# 03-_Power_Supply.net
KiCad netlist of a schematic drawn in Altium Designer
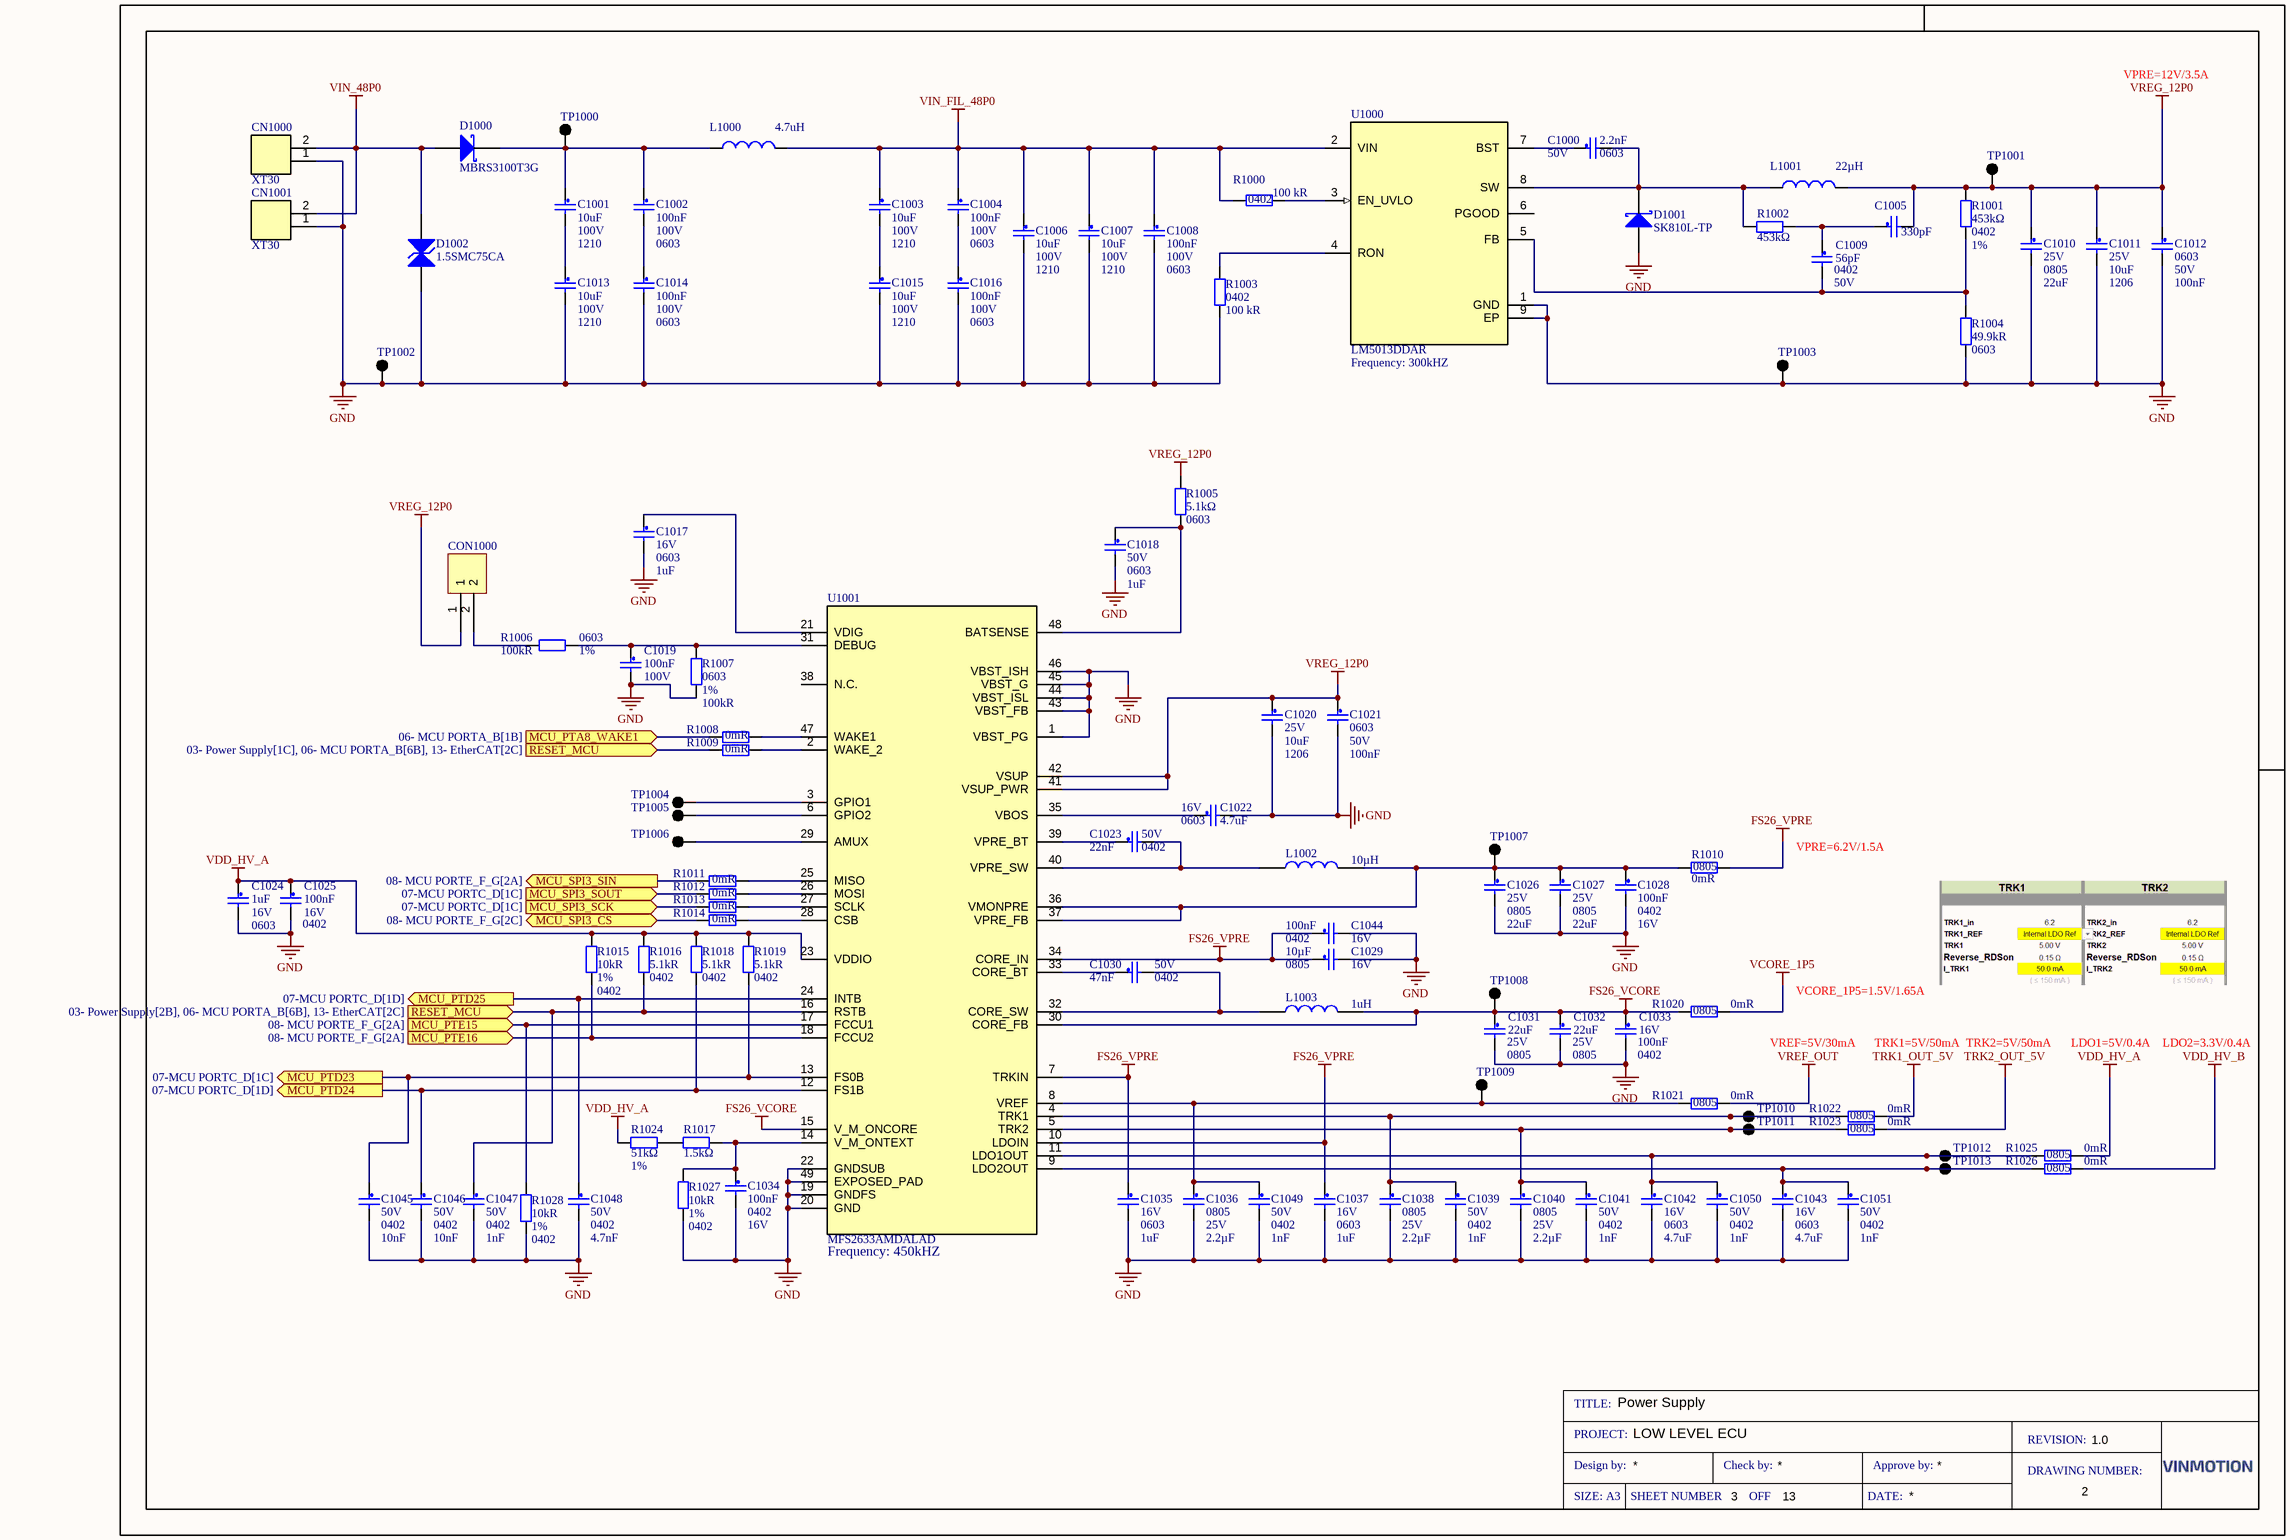
[diagram p0: 03- Power Supply.SchDoc]

(export (version "E")
  (design (tool "Eeschema 10.0.6"))
  (components
    (comp (ref "C1000")
      (value "CL10B222KB8WPNC")
      (footprint "CAP0603")
      (description "CAP CER 2200PF 50V X7R 0603")
      (fields
        (field (name "TOLERANCE") "10%")
        (field (name "VOLTAGE RATING") "50V")
        (field (name "CASE/PACKAGE") "0603")
        (field (name "CAPACITANCE") "2.2nF")
      )
      (libsource (lib "VMO_Lib") (part "CMP-00248-3"))
    )
    (comp (ref "C1001")
      (value "10uF")
      (footprint "CAP1210")
      (description "CAP CER 10UF 100V X7R 1210")
      (fields
        (field (name "MANUFACTURER") "TDK")
        (field (name "MANUFACTURER PART NUMBER") "C3225X7R2A106K250AC")
        (field (name "DC VOLTAGE RATED") "100V")
        (field (name "PACKAGE") "1210")
      )
      (libsource (lib "VMO_Lib") (part "CMP-01079-1"))
    )
    (comp (ref "C1002")
      (value "100nF")
      (footprint "CAP0603")
      (description "CAP CER 0.1UF 100V X7R 0603")
      (fields
        (field (name "MANUFACTURER") "Yageo")
        (field (name "MANUFACTURER PART NUMBER") "CC0603KRX7R0BB104")
        (field (name "RATED DC VOLTAGE (URDC)") "100V")
        (field (name "CASE/PACKAGE") "0603")
      )
      (libsource (lib "VMO_Lib") (part "CMP-01080-1"))
    )
    (comp (ref "C1003")
      (value "10uF")
      (footprint "CAP1210")
      (description "CAP CER 10UF 100V X7R 1210")
      (fields
        (field (name "MANUFACTURER") "TDK")
        (field (name "MANUFACTURER PART NUMBER") "C3225X7R2A106K250AC")
        (field (name "DC VOLTAGE RATED") "100V")
        (field (name "PACKAGE") "1210")
      )
      (libsource (lib "VMO_Lib") (part "CMP-01079-1"))
    )
    (comp (ref "C1004")
      (value "100nF")
      (footprint "CAP0603")
      (description "CAP CER 0.1UF 100V X7R 0603")
      (fields
        (field (name "MANUFACTURER") "Yageo")
        (field (name "MANUFACTURER PART NUMBER") "CC0603KRX7R0BB104")
        (field (name "RATED DC VOLTAGE (URDC)") "100V")
        (field (name "CASE/PACKAGE") "0603")
      )
      (libsource (lib "VMO_Lib") (part "CMP-01080-1"))
    )
    (comp (ref "C1005")
      (value "GCM1885C2A331JA16D")
      (footprint "CAP0603")
      (description "CAP CER 330pF 100V 5% C0G 0603 SMD")
      (fields (field (name "TOLERANCE") "5%") (field (name "CAPACITANCE") "330pF"))
      (libsource (lib "VMO_Lib") (part "CMP-00223-4"))
    )
    (comp (ref "C1006")
      (value "10uF")
      (footprint "CAP1210")
      (description "CAP CER 10UF 100V X7R 1210")
      (fields
        (field (name "MANUFACTURER") "TDK")
        (field (name "MANUFACTURER PART NUMBER") "C3225X7R2A106K250AC")
        (field (name "DC VOLTAGE RATED") "100V")
        (field (name "PACKAGE") "1210")
      )
      (libsource (lib "VMO_Lib") (part "CMP-01079-1"))
    )
    (comp (ref "C1007")
      (value "10uF")
      (footprint "CAP1210")
      (description "CAP CER 10UF 100V X7R 1210")
      (fields
        (field (name "MANUFACTURER") "TDK")
        (field (name "MANUFACTURER PART NUMBER") "C3225X7R2A106K250AC")
        (field (name "DC VOLTAGE RATED") "100V")
        (field (name "PACKAGE") "1210")
      )
      (libsource (lib "VMO_Lib") (part "CMP-01079-1"))
    )
    (comp (ref "C1008")
      (value "100nF")
      (footprint "CAP0603")
      (description "CAP CER 0.1UF 100V X7R 0603")
      (fields
        (field (name "MANUFACTURER") "Yageo")
        (field (name "MANUFACTURER PART NUMBER") "CC0603KRX7R0BB104")
        (field (name "RATED DC VOLTAGE (URDC)") "100V")
        (field (name "CASE/PACKAGE") "0603")
      )
      (libsource (lib "VMO_Lib") (part "CMP-01080-1"))
    )
    (comp (ref "C1009")
      (value "GCM1555C1H560JA16D")
      (footprint "CAP0402")
      (description "CAP CER 56PF 50V C0G/NP0 0402")
      (fields
        (field (name "TOLERANCE") "5%")
        (field (name "CASE/PACKAGE") "0402")
        (field (name "VOLTAGE RATING") "50V")
        (field (name "CAPACITANCE") "56pF")
      )
      (libsource (lib "VMO_Lib") (part "CMP-00911-1"))
    )
    (comp (ref "C1010")
      (value "GRM21BR61E226ME44K")
      (footprint "CAP0805")
      (description "CAP CER 22uF 25V 20% X5R 0805 SMD")
      (fields
        (field (name "TOLERANCE") "20%")
        (field (name "VOLTAGE RATING") "25V")
        (field (name "CASE/PACKAGE") "0805")
        (field (name "CAPACITANCE") "22uF")
      )
      (libsource (lib "VMO_Lib") (part "CMP-ROOT-0068-6"))
    )
    (comp (ref "C1011")
      (value "GCM31CC71E106KA03L")
      (footprint "CAP1206")
      (description "CAP CER 10UF 25V X7S 1206")
      (fields
        (field (name "VOLTAGE RATING (DC)") "25V")
        (field (name "CAPACITANCE") "10uF")
        (field (name "TOLERANCE") "10%")
        (field (name "CASE CODE (IMPERIAL)") "1206")
      )
      (libsource (lib "VMO_Lib") (part "CMP-00214-1"))
    )
    (comp (ref "C1012")
      (value "CL10B104KB8WPNC")
      (footprint "CAP0603")
      (description "CAP CER 0.1UF 50V X7R 0603")
      (fields
        (field (name "TOLERANCE") "10%")
        (field (name "CASE/PACKAGE") "0603")
        (field (name "VOLTAGE RATING") "50V")
        (field (name "CAPACITANCE") "100nF")
      )
      (libsource (lib "VMO_Lib") (part "CMP-00005-5"))
    )
    (comp (ref "C1013")
      (value "10uF")
      (footprint "CAP1210")
      (description "CAP CER 10UF 100V X7R 1210")
      (fields
        (field (name "MANUFACTURER") "TDK")
        (field (name "MANUFACTURER PART NUMBER") "C3225X7R2A106K250AC")
        (field (name "DC VOLTAGE RATED") "100V")
        (field (name "PACKAGE") "1210")
      )
      (libsource (lib "VMO_Lib") (part "CMP-01079-1"))
    )
    (comp (ref "C1014")
      (value "100nF")
      (footprint "CAP0603")
      (description "CAP CER 0.1UF 100V X7R 0603")
      (fields
        (field (name "MANUFACTURER") "Yageo")
        (field (name "MANUFACTURER PART NUMBER") "CC0603KRX7R0BB104")
        (field (name "RATED DC VOLTAGE (URDC)") "100V")
        (field (name "CASE/PACKAGE") "0603")
      )
      (libsource (lib "VMO_Lib") (part "CMP-01080-1"))
    )
    (comp (ref "C1015")
      (value "10uF")
      (footprint "CAP1210")
      (description "CAP CER 10UF 100V X7R 1210")
      (fields
        (field (name "MANUFACTURER") "TDK")
        (field (name "MANUFACTURER PART NUMBER") "C3225X7R2A106K250AC")
        (field (name "DC VOLTAGE RATED") "100V")
        (field (name "PACKAGE") "1210")
      )
      (libsource (lib "VMO_Lib") (part "CMP-01079-1"))
    )
    (comp (ref "C1016")
      (value "100nF")
      (footprint "CAP0603")
      (description "CAP CER 0.1UF 100V X7R 0603")
      (fields
        (field (name "MANUFACTURER") "Yageo")
        (field (name "MANUFACTURER PART NUMBER") "CC0603KRX7R0BB104")
        (field (name "RATED DC VOLTAGE (URDC)") "100V")
        (field (name "CASE/PACKAGE") "0603")
      )
      (libsource (lib "VMO_Lib") (part "CMP-01080-1"))
    )
    (comp (ref "C1017")
      (value "CGA3E1X7R1C105K080AC")
      (footprint "CAP0603")
      (description "CAP CER 1uF 16V X7R 0603")
      (fields
        (field (name "TOLERANCE") "10%")
        (field (name "VOLTAGE RATING") "16V")
        (field (name "CASE/PACKAGE") "0603")
        (field (name "CAPACITANCE") "1uF")
      )
      (libsource (lib "VMO_Lib") (part "CMP-00042-2"))
    )
    (comp (ref "C1018")
      (value "CL10A105KB8NNNC")
      (footprint "CAP0603")
      (description "CAP CER 1UF 50V X5R 0603")
      (fields
        (field (name "TOLERANCE") "10%")
        (field (name "VOLTAGE RATING") "50V")
        (field (name "CASE/PACKAGE") "0603")
        (field (name "CAPACITANCE") "1uF")
      )
      (libsource (lib "VMO_Lib") (part "CMP-00313-1"))
    )
    (comp (ref "C1019")
      (value "100nF")
      (footprint "CAP0603")
      (description "CAP CER 0.1UF 100V X7R 0603")
      (fields
        (field (name "MANUFACTURER") "Yageo")
        (field (name "MANUFACTURER PART NUMBER") "CC0603KRX7R0BB104")
        (field (name "RATED DC VOLTAGE (URDC)") "100V")
      )
      (libsource (lib "VMO_Lib") (part "CMP-01080-1"))
    )
    (comp (ref "C1020")
      (value "GCM31CC71E106KA03L")
      (footprint "CAP1206")
      (description "CAP CER 10UF 25V X7S 1206")
      (fields
        (field (name "VOLTAGE RATING (DC)") "25V")
        (field (name "CAPACITANCE") "10uF")
        (field (name "TOLERANCE") "10%")
        (field (name "CASE CODE (IMPERIAL)") "1206")
      )
      (libsource (lib "VMO_Lib") (part "CMP-00214-1"))
    )
    (comp (ref "C1021")
      (value "CL10B104KB8WPNC")
      (footprint "CAP0603")
      (description "CAP CER 0.1UF 50V X7R 0603")
      (fields
        (field (name "TOLERANCE") "10%")
        (field (name "CASE/PACKAGE") "0603")
        (field (name "VOLTAGE RATING") "50V")
        (field (name "CAPACITANCE") "100nF")
      )
      (libsource (lib "VMO_Lib") (part "CMP-00005-5"))
    )
    (comp (ref "C1022")
      (value "GRT188C81C475KE13D")
      (footprint "CAP0603")
      (description "CAP CER 4.7uF 16V 10% X6S 0603 SMD")
      (fields
        (field (name "TOLERANCE") "10%")
        (field (name "VOLTAGE RATING") "16V")
        (field (name "CASE/PACKAGE") "0603")
        (field (name "CAPACITANCE") "4.7uF")
      )
      (libsource (lib "VMO_Lib") (part "CMP-00351-2"))
    )
    (comp (ref "C1023")
      (value "GCM155R71H223KA55D")
      (footprint "CAP0402")
      (description "CAP CER 0.022UF 50V X7R 0402")
      (fields
        (field (name "TOLERANCE") "10%")
        (field (name "VOLTAGE") "50V")
        (field (name "VOLTAGE RATING") "50V")
        (field (name "CASE/PACKAGE") "0402")
        (field (name "CAPACITANCE") "22nF")
      )
      (libsource (lib "VMO_Lib") (part "CMP-00784-1"))
    )
    (comp (ref "C1024")
      (value "CGA3E1X7R1C105K080AC")
      (footprint "CAP0603")
      (description "CAP CER 1uF 16V X7R 0603")
      (fields
        (field (name "TOLERANCE") "10%")
        (field (name "VOLTAGE RATING") "16V")
        (field (name "CASE/PACKAGE") "0603")
        (field (name "CAPACITANCE") "1uF")
      )
      (libsource (lib "VMO_Lib") (part "CMP-00042-2"))
    )
    (comp (ref "C1025")
      (value "0402YC104KAT2A")
      (footprint "CAP0402")
      (description "CAP CER 0.1UF 16V X7R 0402")
      (fields
        (field (name "CAPACITANCE") "100nF")
        (field (name "CASE/PACKAGE") "0402")
        (field (name "VOLTAGE RATING (DC)") "16V")
      )
      (libsource (lib "VMO_Lib") (part "CMP-00988-1"))
    )
    (comp (ref "C1026")
      (value "GRM21BR61E226ME44K")
      (footprint "CAP0805")
      (description "CAP CER 22uF 25V 20% X5R 0805 SMD")
      (fields
        (field (name "TOLERANCE") "20%")
        (field (name "VOLTAGE RATING") "25V")
        (field (name "CASE/PACKAGE") "0805")
        (field (name "CAPACITANCE") "22uF")
      )
      (libsource (lib "VMO_Lib") (part "CMP-ROOT-0068-6"))
    )
    (comp (ref "C1027")
      (value "GRM21BR61E226ME44K")
      (footprint "CAP0805")
      (description "CAP CER 22uF 25V 20% X5R 0805 SMD")
      (fields
        (field (name "TOLERANCE") "20%")
        (field (name "VOLTAGE RATING") "25V")
        (field (name "CASE/PACKAGE") "0805")
        (field (name "CAPACITANCE") "22uF")
      )
      (libsource (lib "VMO_Lib") (part "CMP-ROOT-0068-6"))
    )
    (comp (ref "C1028")
      (value "0402YC104KAT2A")
      (footprint "CAP0402")
      (description "CAP CER 0.1UF 16V X7R 0402")
      (fields
        (field (name "CAPACITANCE") "100nF")
        (field (name "CASE/PACKAGE") "0402")
        (field (name "VOLTAGE RATING (DC)") "16V")
      )
      (libsource (lib "VMO_Lib") (part "CMP-00988-1"))
    )
    (comp (ref "C1029")
      (value "10µF")
      (footprint "CAP0805")
      (description "CAP CER 10UF 16V X7R 0805")
      (fields
        (field (name "CASE/PACKAGE") "0805")
        (field (name "MANUFACTURER") "Murata")
        (field (name "MANUFACTURER PART NUMBER") "GRM21BZ71C106KE15L")
        (field (name "VOLTAGE RATING") "16V")
      )
      (libsource (lib "VMO_Lib") (part "CMP-01170-1"))
    )
    (comp (ref "C1030")
      (value "UMK105B7473KVHF")
      (footprint "CAP0402")
      (description "CAP CER 0.047UF 50V X7R 0402")
      (fields
        (field (name "TOLERANCE") "10%")
        (field (name "VOLTAGE RATING") "50V")
        (field (name "CASE/PACKAGE") "0402")
        (field (name "CAPACITANCE") "47nF")
      )
      (libsource (lib "VMO_Lib") (part "CMP-00420-2"))
    )
    (comp (ref "C1031")
      (value "GRM21BR61E226ME44K")
      (footprint "CAP0805")
      (description "CAP CER 22uF 25V 20% X5R 0805 SMD")
      (fields
        (field (name "TOLERANCE") "20%")
        (field (name "VOLTAGE RATING") "25V")
        (field (name "CASE/PACKAGE") "0805")
        (field (name "CAPACITANCE") "22uF")
      )
      (libsource (lib "VMO_Lib") (part "CMP-ROOT-0068-6"))
    )
    (comp (ref "C1032")
      (value "GRM21BR61E226ME44K")
      (footprint "CAP0805")
      (description "CAP CER 22uF 25V 20% X5R 0805 SMD")
      (fields
        (field (name "TOLERANCE") "20%")
        (field (name "VOLTAGE RATING") "25V")
        (field (name "CASE/PACKAGE") "0805")
        (field (name "CAPACITANCE") "22uF")
      )
      (libsource (lib "VMO_Lib") (part "CMP-ROOT-0068-6"))
    )
    (comp (ref "C1033")
      (value "0402YC104KAT2A")
      (footprint "CAP0402")
      (description "CAP CER 0.1UF 16V X7R 0402")
      (fields
        (field (name "CAPACITANCE") "100nF")
        (field (name "CASE/PACKAGE") "0402")
        (field (name "VOLTAGE RATING (DC)") "16V")
      )
      (libsource (lib "VMO_Lib") (part "CMP-00988-1"))
    )
    (comp (ref "C1034")
      (value "0402YC104KAT2A")
      (footprint "CAP0402")
      (description "CAP CER 0.1UF 16V X7R 0402")
      (fields
        (field (name "CAPACITANCE") "100nF")
        (field (name "CASE/PACKAGE") "0402")
        (field (name "VOLTAGE RATING (DC)") "16V")
      )
      (libsource (lib "VMO_Lib") (part "CMP-00988-1"))
    )
    (comp (ref "C1035")
      (value "CGA3E1X7R1C105K080AC")
      (footprint "CAP0603")
      (description "CAP CER 1uF 16V X7R 0603")
      (fields
        (field (name "TOLERANCE") "10%")
        (field (name "VOLTAGE RATING") "16V")
        (field (name "CASE/PACKAGE") "0603")
        (field (name "CAPACITANCE") "1uF")
      )
      (libsource (lib "VMO_Lib") (part "CMP-00042-2"))
    )
    (comp (ref "C1036")
      (value "GCM21BR71E225KA73L")
      (footprint "CAP0805")
      (description "CAP CER 2.2UF 25V X7R 0805")
      (fields
        (field (name "TOLERANCE") "10%")
        (field (name "VOLTAGE") "25V")
        (field (name "CASE/PACKAGE") "0805")
        (field (name "VOLTAGE RATING") "25V")
        (field (name "CAPACITANCE") "2.2µF")
      )
      (libsource (lib "VMO_Lib") (part "CMP-00931-1"))
    )
    (comp (ref "C1037")
      (value "CGA3E1X7R1C105K080AC")
      (footprint "CAP0603")
      (description "CAP CER 1uF 16V X7R 0603")
      (fields
        (field (name "TOLERANCE") "10%")
        (field (name "VOLTAGE RATING") "16V")
        (field (name "CASE/PACKAGE") "0603")
        (field (name "CAPACITANCE") "1uF")
      )
      (libsource (lib "VMO_Lib") (part "CMP-00042-2"))
    )
    (comp (ref "C1038")
      (value "GCM21BR71E225KA73L")
      (footprint "CAP0805")
      (description "CAP CER 2.2UF 25V X7R 0805")
      (fields
        (field (name "TOLERANCE") "10%")
        (field (name "VOLTAGE") "25V")
        (field (name "CASE/PACKAGE") "0805")
        (field (name "VOLTAGE RATING") "25V")
        (field (name "CAPACITANCE") "2.2µF")
      )
      (libsource (lib "VMO_Lib") (part "CMP-00931-1"))
    )
    (comp (ref "C1039")
      (value "UMK105B7102KVHF")
      (footprint "CAP0402")
      (description "CAP CER 1nF 50V 10% X7R 0402 SMD")
      (fields
        (field (name "TOLERANCE") "10%")
        (field (name "VOLTAGE RATING") "50V")
        (field (name "CASE/PACKAGE") "0402")
        (field (name "CAPACITANCE") "1nF")
      )
      (libsource (lib "VMO_Lib") (part "CMP-ROOT-0049-5"))
    )
    (comp (ref "C1040")
      (value "GCM21BR71E225KA73L")
      (footprint "CAP0805")
      (description "CAP CER 2.2UF 25V X7R 0805")
      (fields
        (field (name "TOLERANCE") "10%")
        (field (name "VOLTAGE") "25V")
        (field (name "CASE/PACKAGE") "0805")
        (field (name "VOLTAGE RATING") "25V")
        (field (name "CAPACITANCE") "2.2µF")
      )
      (libsource (lib "VMO_Lib") (part "CMP-00931-1"))
    )
    (comp (ref "C1041")
      (value "UMK105B7102KVHF")
      (footprint "CAP0402")
      (description "CAP CER 1nF 50V 10% X7R 0402 SMD")
      (fields
        (field (name "TOLERANCE") "10%")
        (field (name "VOLTAGE RATING") "50V")
        (field (name "CASE/PACKAGE") "0402")
        (field (name "CAPACITANCE") "1nF")
      )
      (libsource (lib "VMO_Lib") (part "CMP-ROOT-0049-5"))
    )
    (comp (ref "C1042")
      (value "GRT188C81C475KE13D")
      (footprint "CAP0603")
      (description "CAP CER 4.7uF 16V 10% X6S 0603 SMD")
      (fields
        (field (name "TOLERANCE") "10%")
        (field (name "VOLTAGE RATING") "16V")
        (field (name "CASE/PACKAGE") "0603")
        (field (name "CAPACITANCE") "4.7uF")
      )
      (libsource (lib "VMO_Lib") (part "CMP-00351-2"))
    )
    (comp (ref "C1043")
      (value "GRT188C81C475KE13D")
      (footprint "CAP0603")
      (description "CAP CER 4.7uF 16V 10% X6S 0603 SMD")
      (fields
        (field (name "TOLERANCE") "10%")
        (field (name "VOLTAGE RATING") "16V")
        (field (name "CASE/PACKAGE") "0603")
        (field (name "CAPACITANCE") "4.7uF")
      )
      (libsource (lib "VMO_Lib") (part "CMP-00351-2"))
    )
    (comp (ref "C1044")
      (value "0402YC104KAT2A")
      (footprint "CAP0402")
      (description "CAP CER 0.1UF 16V X7R 0402")
      (fields
        (field (name "CAPACITANCE") "100nF")
        (field (name "CASE/PACKAGE") "0402")
        (field (name "VOLTAGE RATING (DC)") "16V")
      )
      (libsource (lib "VMO_Lib") (part "CMP-00988-1"))
    )
    (comp (ref "C1045")
      (value "GCM155R71H103KA55D")
      (footprint "CAP0402")
      (description "CAP CER 10000PF 50V X7R 0402")
      (fields
        (field (name "VOLTAGE") "50V")
        (field (name "TOLERANCE") "10%")
        (field (name "VOLTAGE RATING") "50V")
        (field (name "CASE/PACKAGE") "0402")
        (field (name "CAPACITANCE") "10nF")
      )
      (libsource (lib "VMO_Lib") (part "CMP-00887-1"))
    )
    (comp (ref "C1046")
      (value "GCM155R71H103KA55D")
      (footprint "CAP0402")
      (description "CAP CER 10000PF 50V X7R 0402")
      (fields
        (field (name "VOLTAGE") "50V")
        (field (name "TOLERANCE") "10%")
        (field (name "VOLTAGE RATING") "50V")
        (field (name "CASE/PACKAGE") "0402")
        (field (name "CAPACITANCE") "10nF")
      )
      (libsource (lib "VMO_Lib") (part "CMP-00887-1"))
    )
    (comp (ref "C1047")
      (value "UMK105B7102KVHF")
      (footprint "CAP0402")
      (description "CAP CER 1nF 50V 10% X7R 0402 SMD")
      (fields
        (field (name "TOLERANCE") "10%")
        (field (name "VOLTAGE RATING") "50V")
        (field (name "CASE/PACKAGE") "0402")
        (field (name "CAPACITANCE") "1nF")
      )
      (libsource (lib "VMO_Lib") (part "CMP-ROOT-0049-5"))
    )
    (comp (ref "C1048")
      (value "UMK105B7472KVHF")
      (footprint "CAP0402")
      (description "CAP CER 4.7nF 50V 10% X7R 0402 SMD")
      (fields
        (field (name "TOLERANCE") "10%")
        (field (name "VOLTAGE RATING") "50V")
        (field (name "CASE/PACKAGE") "0402")
        (field (name "CAPACITANCE") "4.7nF")
      )
      (libsource (lib "VMO_Lib") (part "CMP-00455-2"))
    )
    (comp (ref "C1049")
      (value "UMK105B7102KVHF")
      (footprint "CAP0402")
      (description "CAP CER 1nF 50V 10% X7R 0402 SMD")
      (fields
        (field (name "TOLERANCE") "10%")
        (field (name "VOLTAGE RATING") "50V")
        (field (name "CASE/PACKAGE") "0402")
        (field (name "CAPACITANCE") "1nF")
      )
      (libsource (lib "VMO_Lib") (part "CMP-ROOT-0049-5"))
    )
    (comp (ref "C1050")
      (value "UMK105B7102KVHF")
      (footprint "CAP0402")
      (description "CAP CER 1nF 50V 10% X7R 0402 SMD")
      (fields
        (field (name "TOLERANCE") "10%")
        (field (name "VOLTAGE RATING") "50V")
        (field (name "CASE/PACKAGE") "0402")
        (field (name "CAPACITANCE") "1nF")
      )
      (libsource (lib "VMO_Lib") (part "CMP-ROOT-0049-5"))
    )
    (comp (ref "C1051")
      (value "UMK105B7102KVHF")
      (footprint "CAP0402")
      (description "CAP CER 1nF 50V 10% X7R 0402 SMD")
      (fields
        (field (name "TOLERANCE") "10%")
        (field (name "VOLTAGE RATING") "50V")
        (field (name "CASE/PACKAGE") "0402")
        (field (name "CAPACITANCE") "1nF")
      )
      (libsource (lib "VMO_Lib") (part "CMP-ROOT-0049-5"))
    )
    (comp (ref "CN1000")
      (value "XT30")
      (footprint "XT30")
      (description "XT30 CONNECTOR")
      (libsource (lib "VMO_Lib") (part "CMP-01151-1"))
    )
    (comp (ref "CN1001")
      (value "XT30")
      (footprint "XT30")
      (description "XT30 CONNECTOR")
      (libsource (lib "VMO_Lib") (part "CMP-01151-1"))
    )
    (comp (ref "CON1000")
      (value "61300211121")
      (footprint "61300211121-Footprint-1")
      (description "CONN HEADER VERT 2POS 2.54MM")
      (libsource (lib "VMO_Lib") (part "CMP-00162-3"))
    )
    (comp (ref "D1000")
      (value "MBRS3100T3G")
      (footprint "DIOM6959X26N")
      (description "DIODE SCHOTTKY 100V 3A SMC")
      (fields (field (name "MANUFACTURER") "onsemi"))
      (libsource (lib "VMO_Lib") (part "CMP-01162-1"))
    )
    (comp (ref "D1001")
      (value "SK810L-TP")
      (footprint "SMC")
      (description "DIODE SCHOTTKY 100V 8A DO214AB")
      (fields (field (name "MANUFACTURER") "MCC"))
      (libsource (lib "VMO_Lib") (part "CMP-01180-1"))
    )
    (comp (ref "D1002")
      (value "1.5SMC75CA")
      (footprint "LITTLEFUSE_DO-214AB (SMCJ)_TPSMD18CA_N")
      (description "TVS DIODE 64.1VWM 103V DO214AB")
      (fields (field (name "MANUFACTURER") "Littelfuse"))
      (libsource (lib "VMO_Lib") (part "CMP-01163-1"))
    )
    (comp (ref "L1000")
      (value "NRS5040T4R7NMGKV")
      (footprint "INDP4949X20N")
      (description "FIXED IND 4.7UH 3.1A 37.7 MOHM")
      (fields (field (name "TOLERANCE") "30%") (field (name "INDUCTANCE") "4.7uH"))
      (libsource (lib "VMO_Lib") (part "CMP-00882-1"))
    )
    (comp (ref "L1001")
      (value "22µH")
      (footprint "INDP11X10X6")
      (description "IND POWER HC 22UH 6A SHLD")
      (fields
        (field (name "MANUFACTURER") "Bourns")
        (field (name "MANUFACTURER PART NUMBER") "SRP1050WA-220M")
      )
      (libsource (lib "VMO_Lib") (part "CMP-01179-1"))
    )
    (comp (ref "L1002")
      (value "10µH")
      (footprint "INDC548X528X510")
      (description "FIXED IND 10UH 4.9A 45MOHM SM")
      (fields
        (field (name "MANUFACTURER") "Coilcraft")
        (field (name "MANUFACTURER PART NUMBER") "XAL5050-103MEC")
      )
      (libsource (lib "VMO_Lib") (part "CMP-01169-1"))
    )
    (comp (ref "L1003")
      (value "1uH")
      (footprint "INDP2016X12N")
      (description "FIXED IND 1UH 3.1A 60 MOHM SMD")
      (fields
        (field (name "MANUFACTURER") "TDK")
        (field (name "MANUFACTURER PART NUMBER") "TFM201610ALMA1R0MTAA")
      )
      (libsource (lib "VMO_Lib") (part "CMP-01171-1"))
    )
    (comp (ref "R1000")
      (value "RK73B1ETTP104J")
      (footprint "RES0402")
      (description "RES 100K OHM 5% 1/10W 0402")
      (fields
        (field (name "TOLERANCE") "5%")
        (field (name "CASE/PACKAGE") "0402")
        (field (name "RESISTANCE") "100 kR")
      )
      (libsource (lib "VMO_Lib") (part "CMP-00899-1"))
    )
    (comp (ref "R1001")
      (value "453kΩ")
      (footprint "RES0402")
      (description "RES 453K OHM 1% 1/16W 0402")
      (fields
        (field (name "CASE/PACKAGE") "0402")
        (field (name "MANUFACTURER") "Yageo Group")
        (field (name "MANUFACTURER PART NUMBER") "RC0402FR-13453KL")
        (field (name "TOLERANCE") "1%")
      )
      (libsource (lib "VMO_Lib") (part "CMP-01181-1"))
    )
    (comp (ref "R1002")
      (value "453kΩ")
      (footprint "RES0603")
      (description "RES 453K OHM 1% 1/10W 0603")
      (fields
        (field (name "MANUFACTURER") "Yageo Group")
        (field (name "MANUFACTURER PART NUMBER") "RC0603FR-07453KL")
      )
      (libsource (lib "VMO_Lib") (part "CMP-01182-1"))
    )
    (comp (ref "R1003")
      (value "RK73B1ETTP104J")
      (footprint "RES0402")
      (description "RES 100K OHM 5% 1/10W 0402")
      (fields
        (field (name "TOLERANCE") "5%")
        (field (name "CASE/PACKAGE") "0402")
        (field (name "RESISTANCE") "100 kR")
      )
      (libsource (lib "") (part "CMP-00899-1_1"))
    )
    (comp (ref "R1004")
      (value "CRCW060349K9FKEAHP")
      (footprint "RES0603")
      (description "RES SMD 49.9K OHM 1% 1/4W 0603")
      (fields
        (field (name "TOLERANCE") "1%")
        (field (name "RESISTANCE") "49.9kR")
        (field (name "CASE/PACKAGE") "0603")
      )
      (libsource (lib "VMO_Lib") (part "CMP-ROOT-0056-10"))
    )
    (comp (ref "R1005")
      (value "5.1kΩ")
      (footprint "RES0603")
      (description "RES 5.1K OHM 5% 1/4W 0603")
      (fields
        (field (name "CASE/PACKAGE") "0603")
        (field (name "MANUFACTURER") "ROHM")
        (field (name "MANUFACTURER PART NUMBER") "ESR03EZPJ512")
      )
      (libsource (lib "VMO_Lib") (part "CMP-01168-1"))
    )
    (comp (ref "R1006")
      (value "RMCF0603FG100K")
      (footprint "RES0603")
      (description "RES 100K OHM 1% 1/10W 0603")
      (fields
        (field (name "CASE/PACKAGE") "0603")
        (field (name "TOLERANCE") "1%")
        (field (name "RESISTANCE") "100kR")
      )
      (libsource (lib "") (part "CMP-00115-2_1"))
    )
    (comp (ref "R1007")
      (value "RMCF0603FG100K")
      (footprint "RES0603")
      (description "RES 100K OHM 1% 1/10W 0603")
      (fields
        (field (name "CASE/PACKAGE") "0603")
        (field (name "TOLERANCE") "1%")
        (field (name "RESISTANCE") "100kR")
      )
      (libsource (lib "VMO_Lib") (part "CMP-00115-2"))
    )
    (comp (ref "R1008")
      (value "RMCF0402ZT0R00")
      (footprint "RES0402")
      (description "RES 0R 1/16W 1% 0402 SMD")
      (fields (field (name "RESISTANCE") "0mR"))
      (libsource (lib "VMO_Lib") (part "CMP-ROOT-0037-10"))
    )
    (comp (ref "R1009")
      (value "RMCF0402ZT0R00")
      (footprint "RES0402")
      (description "RES 0R 1/16W 1% 0402 SMD")
      (fields (field (name "RESISTANCE") "0mR"))
      (libsource (lib "VMO_Lib") (part "CMP-ROOT-0037-10"))
    )
    (comp (ref "R1010")
      (value "RMCF0805ZT0R00")
      (footprint "RES0805")
      (description "RES 0R 1/8W 0% 0805 SMD")
      (fields (field (name "RESISTANCE") "0mR") (field (name "CASE/PACKAGE") "0805"))
      (libsource (lib "VMO_Lib") (part "CMP-00052-9"))
    )
    (comp (ref "R1011")
      (value "RMCF0402ZT0R00")
      (footprint "RES0402")
      (description "RES 0R 1/16W 1% 0402 SMD")
      (fields (field (name "RESISTANCE") "0mR"))
      (libsource (lib "VMO_Lib") (part "CMP-ROOT-0037-10"))
    )
    (comp (ref "R1012")
      (value "RMCF0402ZT0R00")
      (footprint "RES0402")
      (description "RES 0R 1/16W 1% 0402 SMD")
      (fields (field (name "RESISTANCE") "0mR"))
      (libsource (lib "VMO_Lib") (part "CMP-ROOT-0037-10"))
    )
    (comp (ref "R1013")
      (value "RMCF0402ZT0R00")
      (footprint "RES0402")
      (description "RES 0R 1/16W 1% 0402 SMD")
      (fields (field (name "RESISTANCE") "0mR"))
      (libsource (lib "VMO_Lib") (part "CMP-ROOT-0037-10"))
    )
    (comp (ref "R1014")
      (value "RMCF0402ZT0R00")
      (footprint "RES0402")
      (description "RES 0R 1/16W 1% 0402 SMD")
      (fields (field (name "RESISTANCE") "0mR"))
      (libsource (lib "VMO_Lib") (part "CMP-ROOT-0037-10"))
    )
    (comp (ref "R1015")
      (value "10kR")
      (footprint "RES0402")
      (description "RES 10K OHM 1% 1/16W 0402")
      (fields
        (field (name "MANUFACTURER") "Stackpole Electronics")
        (field (name "MANUFACTURER PART NUMBER") "RMCF0402FT10K0")
        (field (name "TOLERANCE") "1%")
        (field (name "CASE/PACKAGE") "0402")
      )
      (libsource (lib "VMO_Lib") (part "CMP-01105-1"))
    )
    (comp (ref "R1016")
      (value "MCR01MZPF5101")
      (footprint "RES0402")
      (description "RES SMD 5.1K OHM 1% 1/16W 0402")
      (fields
        (field (name "TOLERANCE") "1%")
        (field (name "RESISTANCE") "5.1kR")
        (field (name "CASE/PACKAGE") "0402")
      )
      (libsource (lib "VMO_Lib") (part "CMP-00289-1"))
    )
    (comp (ref "R1017")
      (value "1.5kΩ")
      (footprint "RES0402")
      (description "RES 1.5K OHM 1% 1/16W 0402")
      (fields
        (field (name "MANUFACTURER") "Yageo Group")
        (field (name "MANUFACTURER PART NUMBER") "RC0402FR-071K5L")
      )
      (libsource (lib "VMO_Lib") (part "CMP-01196-1"))
    )
    (comp (ref "R1018")
      (value "MCR01MZPF5101")
      (footprint "RES0402")
      (description "RES SMD 5.1K OHM 1% 1/16W 0402")
      (fields
        (field (name "TOLERANCE") "1%")
        (field (name "RESISTANCE") "5.1kR")
        (field (name "CASE/PACKAGE") "0402")
      )
      (libsource (lib "VMO_Lib") (part "CMP-00289-1"))
    )
    (comp (ref "R1019")
      (value "MCR01MZPF5101")
      (footprint "RES0402")
      (description "RES SMD 5.1K OHM 1% 1/16W 0402")
      (fields
        (field (name "TOLERANCE") "1%")
        (field (name "RESISTANCE") "5.1kR")
        (field (name "CASE/PACKAGE") "0402")
      )
      (libsource (lib "VMO_Lib") (part "CMP-00289-1"))
    )
    (comp (ref "R1020")
      (value "RMCF0805ZT0R00")
      (footprint "RES0805")
      (description "RES 0R 1/8W 0% 0805 SMD")
      (fields (field (name "RESISTANCE") "0mR") (field (name "CASE/PACKAGE") "0805"))
      (libsource (lib "VMO_Lib") (part "CMP-00052-9"))
    )
    (comp (ref "R1021")
      (value "RMCF0805ZT0R00")
      (footprint "RES0805")
      (description "RES 0R 1/8W 0% 0805 SMD")
      (fields (field (name "RESISTANCE") "0mR") (field (name "CASE/PACKAGE") "0805"))
      (libsource (lib "VMO_Lib") (part "CMP-00052-9"))
    )
    (comp (ref "R1022")
      (value "RMCF0805ZT0R00")
      (footprint "RES0805")
      (description "RES 0R 1/8W 0% 0805 SMD")
      (fields (field (name "RESISTANCE") "0mR") (field (name "CASE/PACKAGE") "0805"))
      (libsource (lib "VMO_Lib") (part "CMP-00052-9"))
    )
    (comp (ref "R1023")
      (value "RMCF0805ZT0R00")
      (footprint "RES0805")
      (description "RES 0R 1/8W 0% 0805 SMD")
      (fields (field (name "RESISTANCE") "0mR") (field (name "CASE/PACKAGE") "0805"))
      (libsource (lib "VMO_Lib") (part "CMP-00052-9"))
    )
    (comp (ref "R1024")
      (value "51kΩ")
      (footprint "RES0402")
      (description "RES SMD 51K OHM 1% 1/16W 0402")
      (fields
        (field (name "MANUFACTURER") "Yageo Group")
        (field (name "MANUFACTURER PART NUMBER") "AC0402FR-0751KL")
        (field (name "TOLERANCE") "1%")
      )
      (libsource (lib "VMO_Lib") (part "CMP-01195-1"))
    )
    (comp (ref "R1025")
      (value "RMCF0805ZT0R00")
      (footprint "RES0805")
      (description "RES 0R 1/8W 0% 0805 SMD")
      (fields (field (name "RESISTANCE") "0mR") (field (name "CASE/PACKAGE") "0805"))
      (libsource (lib "VMO_Lib") (part "CMP-00052-9"))
    )
    (comp (ref "R1026")
      (value "RMCF0805ZT0R00")
      (footprint "RES0805")
      (description "RES 0R 1/8W 0% 0805 SMD")
      (fields (field (name "RESISTANCE") "0mR") (field (name "CASE/PACKAGE") "0805"))
      (libsource (lib "VMO_Lib") (part "CMP-00052-9"))
    )
    (comp (ref "R1027")
      (value "10kR")
      (footprint "RES0402")
      (description "RES 10K OHM 1% 1/16W 0402")
      (fields
        (field (name "MANUFACTURER") "Stackpole Electronics")
        (field (name "MANUFACTURER PART NUMBER") "RMCF0402FT10K0")
        (field (name "TOLERANCE") "1%")
        (field (name "CASE/PACKAGE") "0402")
      )
      (libsource (lib "VMO_Lib") (part "CMP-01105-1"))
    )
    (comp (ref "R1028")
      (value "10kR")
      (footprint "RES0402")
      (description "RES 10K OHM 1% 1/16W 0402")
      (fields
        (field (name "MANUFACTURER") "Stackpole Electronics")
        (field (name "MANUFACTURER PART NUMBER") "RMCF0402FT10K0")
        (field (name "TOLERANCE") "1%")
        (field (name "CASE/PACKAGE") "0402")
      )
      (libsource (lib "VMO_Lib") (part "CMP-01105-1"))
    )
    (comp (ref "TP1000")
      (value "TP")
      (footprint "TP-SMD-R1")
      (description "Test Point 1x1mm")
      (libsource (lib "VMO_Lib") (part "CMP-ROOT-0080-12"))
    )
    (comp (ref "TP1001")
      (value "TP")
      (footprint "TP-SMD-R1")
      (description "Test Point 1x1mm")
      (libsource (lib "VMO_Lib") (part "CMP-ROOT-0080-12"))
    )
    (comp (ref "TP1002")
      (value "TP")
      (footprint "TP-SMD-R1")
      (description "Test Point 1x1mm")
      (libsource (lib "VMO_Lib") (part "CMP-ROOT-0080-12"))
    )
    (comp (ref "TP1003")
      (value "TP")
      (footprint "TP-SMD-R1")
      (description "Test Point 1x1mm")
      (libsource (lib "VMO_Lib") (part "CMP-ROOT-0080-12"))
    )
    (comp (ref "TP1004")
      (value "TP")
      (footprint "TP-SMD-R1")
      (description "Test Point 1x1mm")
      (libsource (lib "VMO_Lib") (part "CMP-ROOT-0080-12"))
    )
    (comp (ref "TP1005")
      (value "TP")
      (footprint "TP-SMD-R1")
      (description "Test Point 1x1mm")
      (libsource (lib "VMO_Lib") (part "CMP-ROOT-0080-12"))
    )
    (comp (ref "TP1006")
      (value "TP")
      (footprint "TP-SMD-R1")
      (description "Test Point 1x1mm")
      (libsource (lib "VMO_Lib") (part "CMP-ROOT-0080-12"))
    )
    (comp (ref "TP1007")
      (value "TP")
      (footprint "TP-SMD-R1")
      (description "Test Point 1x1mm")
      (libsource (lib "VMO_Lib") (part "CMP-ROOT-0080-12"))
    )
    (comp (ref "TP1008")
      (value "TP")
      (footprint "TP-SMD-R1")
      (description "Test Point 1x1mm")
      (libsource (lib "VMO_Lib") (part "CMP-ROOT-0080-12"))
    )
    (comp (ref "TP1009")
      (value "TP")
      (footprint "TP-SMD-R1")
      (description "Test Point 1x1mm")
      (libsource (lib "VMO_Lib") (part "CMP-ROOT-0080-12"))
    )
    (comp (ref "TP1010")
      (value "TP")
      (footprint "TP-SMD-R1")
      (description "Test Point 1x1mm")
      (libsource (lib "VMO_Lib") (part "CMP-ROOT-0080-12"))
    )
    (comp (ref "TP1011")
      (value "TP")
      (footprint "TP-SMD-R1")
      (description "Test Point 1x1mm")
      (libsource (lib "VMO_Lib") (part "CMP-ROOT-0080-12"))
    )
    (comp (ref "TP1012")
      (value "TP")
      (footprint "TP-SMD-R1")
      (description "Test Point 1x1mm")
      (libsource (lib "VMO_Lib") (part "CMP-ROOT-0080-12"))
    )
    (comp (ref "TP1013")
      (value "TP")
      (footprint "TP-SMD-R1")
      (description "Test Point 1x1mm")
      (libsource (lib "VMO_Lib") (part "CMP-ROOT-0080-12"))
    )
    (comp (ref "U1000")
      (value "LM5013DDAR")
      (footprint "SOIC-8")
      (description "IC REG BUCK ADJ 3.5A 8SOPWR")
      (fields (field (name "MANUFACTURER") "Texas Instruments"))
      (libsource (lib "VMO_Lib") (part "CMP-01178-1"))
    )
    (comp (ref "U1001")
      (value "MFS2633AMDALAD")
      (footprint "48-LQFP Exposed Pad(7x7)")
      (description "SAFETY SYSTEM BASIS CHIP WITH LO")
      (fields (field (name "MANUFACTURER") "NXP Semiconductors"))
      (libsource (lib "VMO_Lib") (part "CMP-01149-1"))
    )
  )
  (nets
    (net (code "1") (name "/MCU_PTA8_WAKE1") (class "Default")
      (node (ref "R1008") (pin "1") (pinfunction "1_1") (pintype "passive"))
    )
    (net (code "2") (name "/MCU_PTD23") (class "Default")
      (node (ref "C1045") (pin "1") (pinfunction "1_1") (pintype "passive"))
      (node (ref "R1019") (pin "1") (pinfunction "1_1") (pintype "passive"))
      (node (ref "U1001") (pin "13") (pinfunction "FS0B_13") (pintype "passive"))
    )
    (net (code "3") (name "/MCU_PTD24") (class "Default")
      (node (ref "C1046") (pin "1") (pinfunction "1_1") (pintype "passive"))
      (node (ref "R1018") (pin "1") (pinfunction "1_1") (pintype "passive"))
      (node (ref "U1001") (pin "12") (pinfunction "FS1B_12") (pintype "passive"))
    )
    (net (code "4") (name "/MCU_PTD25") (class "Default")
      (node (ref "C1048") (pin "1") (pinfunction "1_1") (pintype "passive"))
      (node (ref "U1001") (pin "24") (pinfunction "INTB_24") (pintype "passive"))
    )
    (net (code "5") (name "/MCU_PTE15") (class "Default")
      (node (ref "R1028") (pin "2") (pinfunction "2_2") (pintype "passive"))
      (node (ref "U1001") (pin "17") (pinfunction "FCCU1_17") (pintype "passive"))
    )
    (net (code "6") (name "/MCU_PTE16") (class "Default")
      (node (ref "R1015") (pin "1") (pinfunction "1_1") (pintype "passive"))
      (node (ref "U1001") (pin "18") (pinfunction "FCCU2_18") (pintype "passive"))
    )
    (net (code "7") (name "/MCU_SPI3_CS") (class "Default")
      (node (ref "R1014") (pin "1") (pinfunction "1_1") (pintype "passive"))
    )
    (net (code "8") (name "/MCU_SPI3_SCK") (class "Default")
      (node (ref "R1013") (pin "1") (pinfunction "1_1") (pintype "passive"))
    )
    (net (code "9") (name "/MCU_SPI3_SIN") (class "Default")
      (node (ref "R1011") (pin "1") (pinfunction "1_1") (pintype "passive"))
    )
    (net (code "10") (name "/MCU_SPI3_SOUT") (class "Default")
      (node (ref "R1012") (pin "1") (pinfunction "1_1") (pintype "passive"))
    )
    (net (code "11") (name "/RESET_MCU") (class "Default")
      (node (ref "C1047") (pin "1") (pinfunction "1_1") (pintype "passive"))
      (node (ref "R1009") (pin "1") (pinfunction "1_1") (pintype "passive"))
      (node (ref "R1016") (pin "1") (pinfunction "1_1") (pintype "passive"))
      (node (ref "U1001") (pin "16") (pinfunction "RSTB_16") (pintype "passive"))
    )
    (net (code "12") (name "FS26_VCORE") (class "Default")
      (node (ref "C1031") (pin "1") (pinfunction "1_1") (pintype "passive"))
      (node (ref "C1032") (pin "1") (pinfunction "1_1") (pintype "passive"))
      (node (ref "C1033") (pin "1") (pinfunction "1_1") (pintype "passive"))
      (node (ref "L1003") (pin "2") (pinfunction "2_2") (pintype "passive"))
      (node (ref "R1020") (pin "1") (pinfunction "1_1") (pintype "passive"))
      (node (ref "TP1008") (pin "1") (pinfunction "1_1") (pintype "passive"))
      (node (ref "U1001") (pin "15") (pinfunction "V_M_ONCORE_15") (pintype "passive"))
      (node (ref "U1001") (pin "30") (pinfunction "CORE_FB_30") (pintype "passive"))
    )
    (net (code "13") (name "FS26_VPRE") (class "Default")
      (node (ref "C1029") (pin "1") (pinfunction "1_1") (pintype "passive"))
      (node (ref "C1035") (pin "1") (pinfunction "1_1") (pintype "passive"))
      (node (ref "C1037") (pin "1") (pinfunction "1_1") (pintype "passive"))
      (node (ref "C1044") (pin "1") (pinfunction "1_1") (pintype "passive"))
      (node (ref "R1010") (pin "2") (pinfunction "2_2") (pintype "passive"))
      (node (ref "U1001") (pin "10") (pinfunction "LDOIN_10") (pintype "passive"))
      (node (ref "U1001") (pin "34") (pinfunction "CORE_IN_34") (pintype "passive"))
      (node (ref "U1001") (pin "7") (pinfunction "TRKIN_7") (pintype "passive"))
    )
    (net (code "14") (name "GND") (class "Default")
      (node (ref "C1006") (pin "2") (pinfunction "2_2") (pintype "passive"))
      (node (ref "C1007") (pin "2") (pinfunction "2_2") (pintype "passive"))
      (node (ref "C1008") (pin "2") (pinfunction "2_2") (pintype "passive"))
      (node (ref "C1010") (pin "2") (pinfunction "2_2") (pintype "passive"))
      (node (ref "C1011") (pin "2") (pinfunction "2_2") (pintype "passive"))
      (node (ref "C1012") (pin "2") (pinfunction "2_2") (pintype "passive"))
      (node (ref "C1013") (pin "2") (pinfunction "2_2") (pintype "passive"))
      (node (ref "C1014") (pin "2") (pinfunction "2_2") (pintype "passive"))
      (node (ref "C1015") (pin "2") (pinfunction "2_2") (pintype "passive"))
      (node (ref "C1016") (pin "2") (pinfunction "2_2") (pintype "passive"))
      (node (ref "C1017") (pin "2") (pinfunction "2_2") (pintype "passive"))
      (node (ref "C1018") (pin "2") (pinfunction "2_2") (pintype "passive"))
      (node (ref "C1019") (pin "2") (pinfunction "2_2") (pintype "passive"))
      (node (ref "C1020") (pin "2") (pinfunction "2_2") (pintype "passive"))
      (node (ref "C1021") (pin "2") (pinfunction "2_2") (pintype "passive"))
      (node (ref "C1022") (pin "2") (pinfunction "2_2") (pintype "passive"))
      (node (ref "C1024") (pin "2") (pinfunction "2_2") (pintype "passive"))
      (node (ref "C1025") (pin "2") (pinfunction "2_2") (pintype "passive"))
      (node (ref "C1026") (pin "2") (pinfunction "2_2") (pintype "passive"))
      (node (ref "C1027") (pin "2") (pinfunction "2_2") (pintype "passive"))
      (node (ref "C1028") (pin "2") (pinfunction "2_2") (pintype "passive"))
      (node (ref "C1029") (pin "2") (pinfunction "2_2") (pintype "passive"))
      (node (ref "C1031") (pin "2") (pinfunction "2_2") (pintype "passive"))
      (node (ref "C1032") (pin "2") (pinfunction "2_2") (pintype "passive"))
      (node (ref "C1033") (pin "2") (pinfunction "2_2") (pintype "passive"))
      (node (ref "C1034") (pin "2") (pinfunction "2_2") (pintype "passive"))
      (node (ref "C1035") (pin "2") (pinfunction "2_2") (pintype "passive"))
      (node (ref "C1036") (pin "2") (pinfunction "2_2") (pintype "passive"))
      (node (ref "C1037") (pin "2") (pinfunction "2_2") (pintype "passive"))
      (node (ref "C1038") (pin "2") (pinfunction "2_2") (pintype "passive"))
      (node (ref "C1039") (pin "2") (pinfunction "2_2") (pintype "passive"))
      (node (ref "C1040") (pin "2") (pinfunction "2_2") (pintype "passive"))
      (node (ref "C1041") (pin "2") (pinfunction "2_2") (pintype "passive"))
      (node (ref "C1042") (pin "2") (pinfunction "2_2") (pintype "passive"))
      (node (ref "C1043") (pin "2") (pinfunction "2_2") (pintype "passive"))
      (node (ref "C1044") (pin "2") (pinfunction "2_2") (pintype "passive"))
      (node (ref "C1045") (pin "2") (pinfunction "2_2") (pintype "passive"))
      (node (ref "C1046") (pin "2") (pinfunction "2_2") (pintype "passive"))
      (node (ref "C1047") (pin "2") (pinfunction "2_2") (pintype "passive"))
      (node (ref "C1048") (pin "2") (pinfunction "2_2") (pintype "passive"))
      (node (ref "C1049") (pin "2") (pinfunction "2_2") (pintype "passive"))
      (node (ref "C1050") (pin "2") (pinfunction "2_2") (pintype "passive"))
      (node (ref "C1051") (pin "2") (pinfunction "2_2") (pintype "passive"))
      (node (ref "CN1000") (pin "1") (pinfunction "1_1") (pintype "passive"))
      (node (ref "CN1001") (pin "1") (pinfunction "1_1") (pintype "passive"))
      (node (ref "D1001") (pin "2") (pinfunction "A_2") (pintype "passive"))
      (node (ref "D1002") (pin "2") (pinfunction "2_2") (pintype "passive"))
      (node (ref "R1003") (pin "1") (pinfunction "1_1") (pintype "passive"))
      (node (ref "R1004") (pin "1") (pinfunction "1_1") (pintype "passive"))
      (node (ref "R1007") (pin "1") (pinfunction "1_1") (pintype "passive"))
      (node (ref "R1027") (pin "1") (pinfunction "1_1") (pintype "passive"))
      (node (ref "R1028") (pin "1") (pinfunction "1_1") (pintype "passive"))
      (node (ref "TP1002") (pin "1") (pinfunction "1_1") (pintype "passive"))
      (node (ref "TP1003") (pin "1") (pinfunction "1_1") (pintype "passive"))
      (node (ref "U1000") (pin "1") (pinfunction "GND_1") (pintype "power_in"))
      (node (ref "U1000") (pin "9") (pinfunction "EP_9") (pintype "passive"))
      (node (ref "U1001") (pin "1") (pinfunction "VBST_PG_1") (pintype "passive"))
      (node (ref "U1001") (pin "19") (pinfunction "GNDFS_19") (pintype "passive"))
      (node (ref "U1001") (pin "20") (pinfunction "GND_20") (pintype "passive"))
      (node (ref "U1001") (pin "22") (pinfunction "GNDSUB_22") (pintype "passive"))
      (node (ref "U1001") (pin "43") (pinfunction "VBST_FB_43") (pintype "passive"))
      (node (ref "U1001") (pin "44") (pinfunction "VBST_ISL_44") (pintype "passive"))
      (node (ref "U1001") (pin "45") (pinfunction "VBST_G_45") (pintype "passive"))
      (node (ref "U1001") (pin "46") (pinfunction "VBST_ISH_46") (pintype "passive"))
      (node (ref "U1001") (pin "49") (pinfunction "EXPOSED_PAD_49") (pintype "passive"))
    )
    (net (code "15") (name "Net-(C1001-Pad2)") (class "Default")
      (node (ref "C1001") (pin "2") (pinfunction "2_2") (pintype "passive"))
      (node (ref "C1013") (pin "1") (pinfunction "1_1") (pintype "passive"))
    )
    (net (code "16") (name "Net-(C1002-Pad2)") (class "Default")
      (node (ref "C1002") (pin "2") (pinfunction "2_2") (pintype "passive"))
      (node (ref "C1014") (pin "1") (pinfunction "1_1") (pintype "passive"))
    )
    (net (code "17") (name "Net-(C1003-Pad2)") (class "Default")
      (node (ref "C1003") (pin "2") (pinfunction "2_2") (pintype "passive"))
      (node (ref "C1015") (pin "1") (pinfunction "1_1") (pintype "passive"))
    )
    (net (code "18") (name "Net-(C1004-Pad2)") (class "Default")
      (node (ref "C1004") (pin "2") (pinfunction "2_2") (pintype "passive"))
      (node (ref "C1016") (pin "1") (pinfunction "1_1") (pintype "passive"))
    )
    (net (code "19") (name "Net-(C1005-Pad1)") (class "Default")
      (node (ref "C1005") (pin "1") (pinfunction "1_1") (pintype "passive"))
      (node (ref "C1009") (pin "1") (pinfunction "1_1") (pintype "passive"))
      (node (ref "R1002") (pin "2") (pinfunction "2_2") (pintype "passive"))
    )
    (net (code "20") (name "Net-(CON1000-Pad2)") (class "Default")
      (node (ref "CON1000") (pin "2") (pinfunction "2_2") (pintype "passive"))
      (node (ref "R1006") (pin "1") (pinfunction "1_1") (pintype "passive"))
    )
    (net (code "21") (name "Net-(D1000-K)") (class "Default")
      (node (ref "C1001") (pin "1") (pinfunction "1_1") (pintype "passive"))
      (node (ref "C1002") (pin "1") (pinfunction "1_1") (pintype "passive"))
      (node (ref "D1000") (pin "1") (pinfunction "K_1") (pintype "passive"))
      (node (ref "L1000") (pin "1") (pinfunction "1_1") (pintype "passive"))
      (node (ref "TP1000") (pin "1") (pinfunction "1_1") (pintype "passive"))
    )
    (net (code "22") (name "Net-(D1001-K)") (class "Default")
      (node (ref "C1000") (pin "2") (pinfunction "2_2") (pintype "passive"))
      (node (ref "D1001") (pin "1") (pinfunction "K_1") (pintype "passive"))
      (node (ref "L1001") (pin "1") (pinfunction "1_1") (pintype "passive"))
      (node (ref "R1002") (pin "1") (pinfunction "1_1") (pintype "passive"))
      (node (ref "U1000") (pin "8") (pinfunction "SW_8") (pintype "power_in"))
    )
    (net (code "23") (name "Net-(R1017-Pad2)") (class "Default")
      (node (ref "R1017") (pin "2") (pinfunction "2_2") (pintype "passive"))
      (node (ref "R1024") (pin "1") (pinfunction "1_1") (pintype "passive"))
    )
    (net (code "24") (name "Net-(U1000-BST)") (class "Default")
      (node (ref "C1000") (pin "1") (pinfunction "1_1") (pintype "passive"))
      (node (ref "U1000") (pin "7") (pinfunction "BST_7") (pintype "power_in"))
    )
    (net (code "25") (name "Net-(U1000-EN_UVLO)") (class "Default")
      (node (ref "R1000") (pin "2") (pinfunction "2_2") (pintype "passive"))
      (node (ref "U1000") (pin "3") (pinfunction "EN_UVLO_3") (pintype "input"))
    )
    (net (code "26") (name "Net-(U1000-FB)") (class "Default")
      (node (ref "C1009") (pin "2") (pinfunction "2_2") (pintype "passive"))
      (node (ref "R1001") (pin "1") (pinfunction "1_1") (pintype "passive"))
      (node (ref "R1004") (pin "2") (pinfunction "2_2") (pintype "passive"))
      (node (ref "U1000") (pin "5") (pinfunction "FB_5") (pintype "passive"))
    )
    (net (code "27") (name "Net-(U1000-RON)") (class "Default")
      (node (ref "R1003") (pin "2") (pinfunction "2_2") (pintype "passive"))
      (node (ref "U1000") (pin "4") (pinfunction "RON_4") (pintype "passive"))
    )
    (net (code "28") (name "Net-(U1001-AMUX)") (class "Default")
      (node (ref "TP1006") (pin "1") (pinfunction "1_1") (pintype "passive"))
      (node (ref "U1001") (pin "29") (pinfunction "AMUX_29") (pintype "passive"))
    )
    (net (code "29") (name "Net-(U1001-BATSENSE)") (class "Default")
      (node (ref "C1018") (pin "1") (pinfunction "1_1") (pintype "passive"))
      (node (ref "R1005") (pin "1") (pinfunction "1_1") (pintype "passive"))
      (node (ref "U1001") (pin "48") (pinfunction "BATSENSE_48") (pintype "passive"))
    )
    (net (code "30") (name "Net-(U1001-CORE_BT)") (class "Default")
      (node (ref "C1030") (pin "1") (pinfunction "1_1") (pintype "passive"))
      (node (ref "U1001") (pin "33") (pinfunction "CORE_BT_33") (pintype "passive"))
    )
    (net (code "31") (name "Net-(U1001-CORE_SW)") (class "Default")
      (node (ref "C1030") (pin "2") (pinfunction "2_2") (pintype "passive"))
      (node (ref "L1003") (pin "1") (pinfunction "1_1") (pintype "passive"))
      (node (ref "U1001") (pin "32") (pinfunction "CORE_SW_32") (pintype "passive"))
    )
    (net (code "32") (name "Net-(U1001-CSB)") (class "Default")
      (node (ref "R1014") (pin "2") (pinfunction "2_2") (pintype "passive"))
      (node (ref "U1001") (pin "28") (pinfunction "CSB_28") (pintype "passive"))
    )
    (net (code "33") (name "Net-(U1001-DEBUG)") (class "Default")
      (node (ref "C1019") (pin "1") (pinfunction "1_1") (pintype "passive"))
      (node (ref "R1006") (pin "2") (pinfunction "2_2") (pintype "passive"))
      (node (ref "R1007") (pin "2") (pinfunction "2_2") (pintype "passive"))
      (node (ref "U1001") (pin "31") (pinfunction "DEBUG_31") (pintype "passive"))
    )
    (net (code "34") (name "Net-(U1001-GPIO1)") (class "Default")
      (node (ref "TP1004") (pin "1") (pinfunction "1_1") (pintype "passive"))
      (node (ref "U1001") (pin "3") (pinfunction "GPIO1_3") (pintype "passive"))
    )
    (net (code "35") (name "Net-(U1001-GPIO2)") (class "Default")
      (node (ref "TP1005") (pin "1") (pinfunction "1_1") (pintype "passive"))
      (node (ref "U1001") (pin "6") (pinfunction "GPIO2_6") (pintype "passive"))
    )
    (net (code "36") (name "Net-(U1001-LDO1OUT)") (class "Default")
      (node (ref "C1042") (pin "1") (pinfunction "1_1") (pintype "passive"))
      (node (ref "C1050") (pin "1") (pinfunction "1_1") (pintype "passive"))
      (node (ref "R1025") (pin "1") (pinfunction "1_1") (pintype "passive"))
      (node (ref "TP1012") (pin "1") (pinfunction "1_1") (pintype "passive"))
      (node (ref "U1001") (pin "11") (pinfunction "LDO1OUT_11") (pintype "passive"))
    )
    (net (code "37") (name "Net-(U1001-LDO2OUT)") (class "Default")
      (node (ref "C1043") (pin "1") (pinfunction "1_1") (pintype "passive"))
      (node (ref "C1051") (pin "1") (pinfunction "1_1") (pintype "passive"))
      (node (ref "R1026") (pin "1") (pinfunction "1_1") (pintype "passive"))
      (node (ref "TP1013") (pin "1") (pinfunction "1_1") (pintype "passive"))
      (node (ref "U1001") (pin "9") (pinfunction "LDO2OUT_9") (pintype "passive"))
    )
    (net (code "38") (name "Net-(U1001-MISO)") (class "Default")
      (node (ref "R1011") (pin "2") (pinfunction "2_2") (pintype "passive"))
      (node (ref "U1001") (pin "25") (pinfunction "MISO_25") (pintype "passive"))
    )
    (net (code "39") (name "Net-(U1001-MOSI)") (class "Default")
      (node (ref "R1012") (pin "2") (pinfunction "2_2") (pintype "passive"))
      (node (ref "U1001") (pin "26") (pinfunction "MOSI_26") (pintype "passive"))
    )
    (net (code "40") (name "Net-(U1001-SCLK)") (class "Default")
      (node (ref "R1013") (pin "2") (pinfunction "2_2") (pintype "passive"))
      (node (ref "U1001") (pin "27") (pinfunction "SCLK_27") (pintype "passive"))
    )
    (net (code "41") (name "Net-(U1001-TRK1)") (class "Default")
      (node (ref "C1038") (pin "1") (pinfunction "1_1") (pintype "passive"))
      (node (ref "C1039") (pin "1") (pinfunction "1_1") (pintype "passive"))
      (node (ref "R1022") (pin "1") (pinfunction "1_1") (pintype "passive"))
      (node (ref "TP1010") (pin "1") (pinfunction "1_1") (pintype "passive"))
      (node (ref "U1001") (pin "4") (pinfunction "TRK1_4") (pintype "passive"))
    )
    (net (code "42") (name "Net-(U1001-TRK2)") (class "Default")
      (node (ref "C1040") (pin "1") (pinfunction "1_1") (pintype "passive"))
      (node (ref "C1041") (pin "1") (pinfunction "1_1") (pintype "passive"))
      (node (ref "R1023") (pin "1") (pinfunction "1_1") (pintype "passive"))
      (node (ref "TP1011") (pin "1") (pinfunction "1_1") (pintype "passive"))
      (node (ref "U1001") (pin "5") (pinfunction "TRK2_5") (pintype "passive"))
    )
    (net (code "43") (name "Net-(U1001-VBOS)") (class "Default")
      (node (ref "C1022") (pin "1") (pinfunction "1_1") (pintype "passive"))
      (node (ref "U1001") (pin "35") (pinfunction "VBOS_35") (pintype "passive"))
    )
    (net (code "44") (name "Net-(U1001-VDIG)") (class "Default")
      (node (ref "C1017") (pin "1") (pinfunction "1_1") (pintype "passive"))
      (node (ref "U1001") (pin "21") (pinfunction "VDIG_21") (pintype "passive"))
    )
    (net (code "45") (name "Net-(U1001-VMONPRE)") (class "Default")
      (node (ref "C1026") (pin "1") (pinfunction "1_1") (pintype "passive"))
      (node (ref "C1027") (pin "1") (pinfunction "1_1") (pintype "passive"))
      (node (ref "C1028") (pin "1") (pinfunction "1_1") (pintype "passive"))
      (node (ref "L1002") (pin "2") (pinfunction "2_2") (pintype "passive"))
      (node (ref "R1010") (pin "1") (pinfunction "1_1") (pintype "passive"))
      (node (ref "TP1007") (pin "1") (pinfunction "1_1") (pintype "passive"))
      (node (ref "U1001") (pin "36") (pinfunction "VMONPRE_36") (pintype "passive"))
      (node (ref "U1001") (pin "37") (pinfunction "VPRE_FB_37") (pintype "passive"))
    )
    (net (code "46") (name "Net-(U1001-VPRE_BT)") (class "Default")
      (node (ref "C1023") (pin "1") (pinfunction "1_1") (pintype "passive"))
      (node (ref "U1001") (pin "39") (pinfunction "VPRE_BT_39") (pintype "passive"))
    )
    (net (code "47") (name "Net-(U1001-VPRE_SW)") (class "Default")
      (node (ref "C1023") (pin "2") (pinfunction "2_2") (pintype "passive"))
      (node (ref "L1002") (pin "1") (pinfunction "1_1") (pintype "passive"))
      (node (ref "U1001") (pin "40") (pinfunction "VPRE_SW_40") (pintype "passive"))
    )
    (net (code "48") (name "Net-(U1001-VREF)") (class "Default")
      (node (ref "C1036") (pin "1") (pinfunction "1_1") (pintype "passive"))
      (node (ref "C1049") (pin "1") (pinfunction "1_1") (pintype "passive"))
      (node (ref "R1021") (pin "1") (pinfunction "1_1") (pintype "passive"))
      (node (ref "TP1009") (pin "1") (pinfunction "1_1") (pintype "passive"))
      (node (ref "U1001") (pin "8") (pinfunction "VREF_8") (pintype "passive"))
    )
    (net (code "49") (name "Net-(U1001-V_M_ONTEXT)") (class "Default")
      (node (ref "C1034") (pin "1") (pinfunction "1_1") (pintype "passive"))
      (node (ref "R1017") (pin "1") (pinfunction "1_1") (pintype "passive"))
      (node (ref "R1027") (pin "2") (pinfunction "2_2") (pintype "passive"))
      (node (ref "U1001") (pin "14") (pinfunction "V_M_ONTEXT_14") (pintype "passive"))
    )
    (net (code "50") (name "Net-(U1001-WAKE1)") (class "Default")
      (node (ref "R1008") (pin "2") (pinfunction "2_2") (pintype "passive"))
      (node (ref "U1001") (pin "47") (pinfunction "WAKE1_47") (pintype "passive"))
    )
    (net (code "51") (name "Net-(U1001-WAKE_2)") (class "Default")
      (node (ref "R1009") (pin "2") (pinfunction "2_2") (pintype "passive"))
      (node (ref "U1001") (pin "2") (pinfunction "WAKE_2_2") (pintype "passive"))
    )
    (net (code "52") (name "TRK1_OUT_5V") (class "Default")
      (node (ref "R1022") (pin "2") (pinfunction "2_2") (pintype "passive"))
    )
    (net (code "53") (name "TRK2_OUT_5V") (class "Default")
      (node (ref "R1023") (pin "2") (pinfunction "2_2") (pintype "passive"))
    )
    (net (code "54") (name "VCORE_1P5") (class "Default")
      (node (ref "R1020") (pin "2") (pinfunction "2_2") (pintype "passive"))
    )
    (net (code "55") (name "VDD_HV_A") (class "Default")
      (node (ref "C1024") (pin "1") (pinfunction "1_1") (pintype "passive"))
      (node (ref "C1025") (pin "1") (pinfunction "1_1") (pintype "passive"))
      (node (ref "R1015") (pin "2") (pinfunction "2_2") (pintype "passive"))
      (node (ref "R1016") (pin "2") (pinfunction "2_2") (pintype "passive"))
      (node (ref "R1018") (pin "2") (pinfunction "2_2") (pintype "passive"))
      (node (ref "R1019") (pin "2") (pinfunction "2_2") (pintype "passive"))
      (node (ref "R1024") (pin "2") (pinfunction "2_2") (pintype "passive"))
      (node (ref "R1025") (pin "2") (pinfunction "2_2") (pintype "passive"))
      (node (ref "U1001") (pin "23") (pinfunction "VDDIO_23") (pintype "passive"))
    )
    (net (code "56") (name "VDD_HV_B") (class "Default")
      (node (ref "R1026") (pin "2") (pinfunction "2_2") (pintype "passive"))
    )
    (net (code "57") (name "VIN_48P0") (class "Default")
      (node (ref "CN1000") (pin "2") (pinfunction "2_2") (pintype "passive"))
      (node (ref "CN1001") (pin "2") (pinfunction "2_2") (pintype "passive"))
      (node (ref "D1000") (pin "2") (pinfunction "A_2") (pintype "passive"))
      (node (ref "D1002") (pin "1") (pinfunction "1_1") (pintype "passive"))
    )
    (net (code "58") (name "VIN_FIL_48P0") (class "Default")
      (node (ref "C1003") (pin "1") (pinfunction "1_1") (pintype "passive"))
      (node (ref "C1004") (pin "1") (pinfunction "1_1") (pintype "passive"))
      (node (ref "C1006") (pin "1") (pinfunction "1_1") (pintype "passive"))
      (node (ref "C1007") (pin "1") (pinfunction "1_1") (pintype "passive"))
      (node (ref "C1008") (pin "1") (pinfunction "1_1") (pintype "passive"))
      (node (ref "L1000") (pin "2") (pinfunction "2_2") (pintype "passive"))
      (node (ref "R1000") (pin "1") (pinfunction "1_1") (pintype "passive"))
      (node (ref "U1000") (pin "2") (pinfunction "VIN_2") (pintype "power_in"))
    )
    (net (code "59") (name "VREF_OUT") (class "Default")
      (node (ref "R1021") (pin "2") (pinfunction "2_2") (pintype "passive"))
    )
    (net (code "60") (name "VREG_12P0") (class "Default")
      (node (ref "C1005") (pin "2") (pinfunction "2_2") (pintype "passive"))
      (node (ref "C1010") (pin "1") (pinfunction "1_1") (pintype "passive"))
      (node (ref "C1011") (pin "1") (pinfunction "1_1") (pintype "passive"))
      (node (ref "C1012") (pin "1") (pinfunction "1_1") (pintype "passive"))
      (node (ref "C1020") (pin "1") (pinfunction "1_1") (pintype "passive"))
      (node (ref "C1021") (pin "1") (pinfunction "1_1") (pintype "passive"))
      (node (ref "CON1000") (pin "1") (pinfunction "1_1") (pintype "passive"))
      (node (ref "L1001") (pin "2") (pinfunction "2_2") (pintype "passive"))
      (node (ref "R1001") (pin "2") (pinfunction "2_2") (pintype "passive"))
      (node (ref "R1005") (pin "2") (pinfunction "2_2") (pintype "passive"))
      (node (ref "TP1001") (pin "1") (pinfunction "1_1") (pintype "passive"))
      (node (ref "U1001") (pin "41") (pinfunction "VSUP_PWR_41") (pintype "passive"))
      (node (ref "U1001") (pin "42") (pinfunction "VSUP_42") (pintype "passive"))
    )
    (net (code "61") (name "unconnected-(U1000-PGOOD-Pad6)") (class "Default")
      (node (ref "U1000") (pin "6") (pinfunction "PGOOD_6") (pintype "open_collector"))
    )
    (net (code "62") (name "unconnected-(U1001-N.C.-Pad38)") (class "Default")
      (node (ref "U1001") (pin "38") (pinfunction "N.C._38") (pintype "passive"))
    )
  )
)
